# LNA_BFU550.net
KiCad netlist of a schematic drawn in Altium Designer
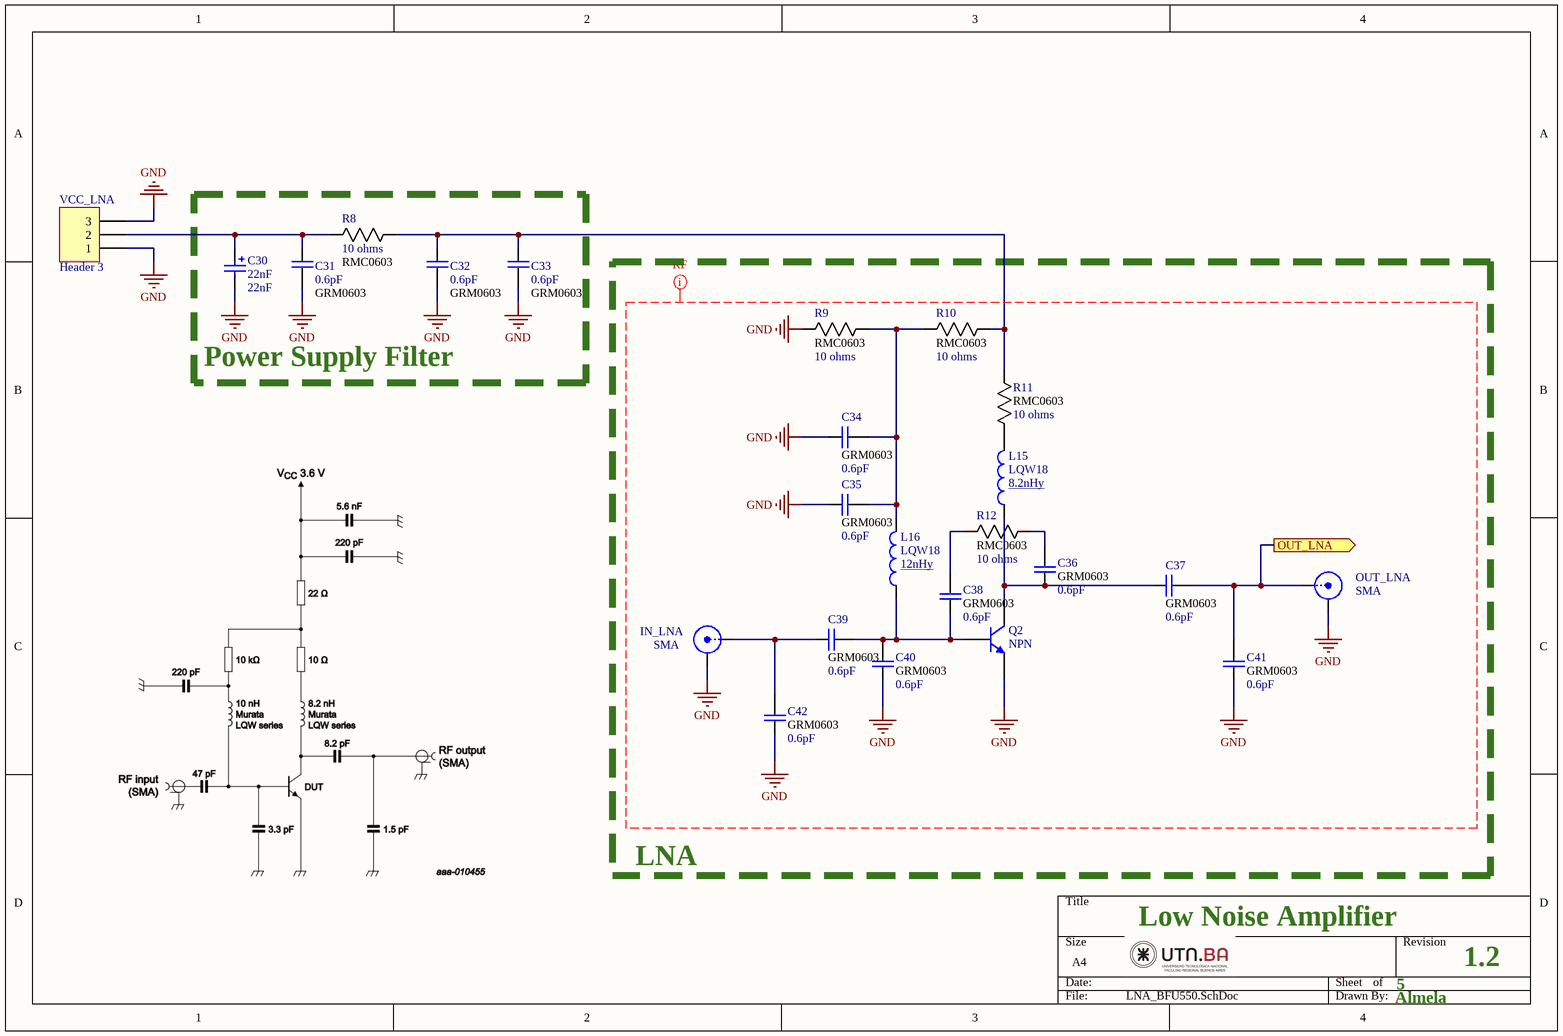
[diagram p0: LNA_BFU550.SchDoc]

(export (version "E")
  (design (tool "Eeschema 10.0.6"))
  (components
    (comp (ref "C30")
      (value "22nF")
      (footprint "6-0805_N")
      (description "Polarized Capacitor (Axial)")
      (fields (field (name "ALTIUM_VALUE") "22nF") (field (name "PUBLISHER") "Altium Limited"))
      (libsource (lib "PCB_Project") (part "Cap Pol2_1"))
    )
    (comp (ref "C31")
      (value "0.6pF")
      (footprint "GRM0603")
      (description "Capacitor GRM18 0603")
      (fields (field (name "Comment") "Cap 0603") (field (name "PUBLISHER") "Altium Limited"))
      (libsource (lib "Radar_RF_EAIII") (part "Cap"))
    )
    (comp (ref "C32")
      (value "0.6pF")
      (footprint "GRM0603")
      (description "Capacitor GRM18 0603")
      (fields (field (name "Comment") "Cap 0603") (field (name "PUBLISHER") "Altium Limited"))
      (libsource (lib "Radar_RF_EAIII") (part "Cap"))
    )
    (comp (ref "C33")
      (value "0.6pF")
      (footprint "GRM0603")
      (description "Capacitor GRM18 0603")
      (fields (field (name "Comment") "Cap 0603") (field (name "PUBLISHER") "Altium Limited"))
      (libsource (lib "Radar_RF_EAIII") (part "Cap"))
    )
    (comp (ref "C34")
      (value "0.6pF")
      (footprint "GRM0603")
      (description "Capacitor GRM18 0603")
      (fields (field (name "Comment") "Cap 0603") (field (name "PUBLISHER") "Altium Limited"))
      (libsource (lib "Radar_RF_EAIII") (part "Cap"))
    )
    (comp (ref "C35")
      (value "0.6pF")
      (footprint "GRM0603")
      (description "Capacitor GRM18 0603")
      (fields (field (name "Comment") "Cap 0603") (field (name "PUBLISHER") "Altium Limited"))
      (libsource (lib "Radar_RF_EAIII") (part "Cap"))
    )
    (comp (ref "C36")
      (value "0.6pF")
      (footprint "GRM0603")
      (description "Capacitor GRM18 0603")
      (fields (field (name "Comment") "Cap 0603") (field (name "PUBLISHER") "Altium Limited"))
      (libsource (lib "Radar_RF_EAIII") (part "Cap"))
    )
    (comp (ref "C37")
      (value "0.6pF")
      (footprint "GRM0603")
      (description "Capacitor GRM18 0603")
      (fields (field (name "Comment") "Cap 0603") (field (name "PUBLISHER") "Altium Limited"))
      (libsource (lib "Radar_RF_EAIII") (part "Cap"))
    )
    (comp (ref "C38")
      (value "0.6pF")
      (footprint "GRM0603")
      (description "Capacitor GRM18 0603")
      (fields (field (name "Comment") "Cap 0603") (field (name "PUBLISHER") "Altium Limited"))
      (libsource (lib "Radar_RF_EAIII") (part "Cap"))
    )
    (comp (ref "C39")
      (value "0.6pF")
      (footprint "GRM0603")
      (description "Capacitor GRM18 0603")
      (fields (field (name "Comment") "Cap 0603") (field (name "PUBLISHER") "Altium Limited"))
      (libsource (lib "Radar_RF_EAIII") (part "Cap"))
    )
    (comp (ref "C40")
      (value "0.6pF")
      (footprint "GRM0603")
      (description "Capacitor GRM18 0603")
      (fields (field (name "Comment") "Cap 0603") (field (name "PUBLISHER") "Altium Limited"))
      (libsource (lib "Radar_RF_EAIII") (part "Cap"))
    )
    (comp (ref "C41")
      (value "0.6pF")
      (footprint "GRM0603")
      (description "Capacitor GRM18 0603")
      (fields (field (name "Comment") "Cap 0603") (field (name "PUBLISHER") "Altium Limited"))
      (libsource (lib "Radar_RF_EAIII") (part "Cap"))
    )
    (comp (ref "C42")
      (value "0.6pF")
      (footprint "GRM0603")
      (description "Capacitor GRM18 0603")
      (fields (field (name "Comment") "Cap 0603") (field (name "PUBLISHER") "Altium Limited"))
      (libsource (lib "Radar_RF_EAIII") (part "Cap"))
    )
    (comp (ref "IN_LNA")
      (value "SMA")
      (footprint "SMA-142-0701-851")
      (description "SMB Straight Connector")
      (fields (field (name "PUBLISHER") "Altium Limited"))
      (libsource (lib "PCB_Project") (part "SMB"))
    )
    (comp (ref "L15")
      (value "LQW18")
      (footprint "INDC1608X100N")
      (description "Inductor LQW Package: 0603 (1608)")
      (fields
        (field (name "MP") "LQW18ANR47J00D")
        (field (name "MF") "Murata")
        (field (name "ALTIUM_VALUE") "8.2nHy")
      )
      (libsource (lib "Radar_RF_EAIII") (part "LQW18_1"))
    )
    (comp (ref "L16")
      (value "LQW18")
      (footprint "INDC1608X100N")
      (description "Inductor LQW Package: 0603 (1608)")
      (fields
        (field (name "MP") "LQW18ANR47J00D")
        (field (name "MF") "Murata")
        (field (name "ALTIUM_VALUE") "12nHy")
      )
      (libsource (lib "Radar_RF_EAIII") (part "LQW18_1"))
    )
    (comp (ref "OUT_LNA")
      (value "SMA")
      (footprint "SMA-142-0701-851")
      (description "SMB Straight Connector")
      (fields (field (name "PUBLISHER") "Altium Limited"))
      (libsource (lib "PCB_Project") (part "SMB"))
    )
    (comp (ref "Q2")
      (value "NPN")
      (footprint "SOT23_N")
      (description "NPN Bipolar Transistor")
      (fields (field (name "PUBLISHER") "Altium Limited"))
      (libsource (lib "Radar_RF_EAIII") (part "BFU550A"))
    )
    (comp (ref "R8")
      (value "10 ohms")
      (footprint "RMC0603")
      (description "Resistor RMC0603")
      (fields (field (name "Comment") "Resistor"))
      (libsource (lib "Radar_RF_EAIII") (part "Resistor"))
    )
    (comp (ref "R9")
      (value "10 ohms")
      (footprint "RMC0603")
      (description "Resistor RMC0603")
      (fields (field (name "Comment") "Resistor"))
      (libsource (lib "Radar_RF_EAIII") (part "Resistor"))
    )
    (comp (ref "R10")
      (value "10 ohms")
      (footprint "RMC0603")
      (description "Resistor RMC0603")
      (fields (field (name "Comment") "Resistor"))
      (libsource (lib "Radar_RF_EAIII") (part "Resistor"))
    )
    (comp (ref "R11")
      (value "10 ohms")
      (footprint "RMC0603")
      (description "Resistor RMC0603")
      (fields (field (name "Comment") "Resistor"))
      (libsource (lib "Radar_RF_EAIII") (part "Resistor"))
    )
    (comp (ref "R12")
      (value "10 ohms")
      (footprint "RMC0603")
      (description "Resistor RMC0603")
      (fields (field (name "Comment") "Resistor"))
      (libsource (lib "Radar_RF_EAIII") (part "Resistor"))
    )
    (comp (ref "VCC_LNA")
      (value "Header 3")
      (footprint "HDR1X3")
      (description "Header, 3-Pin")
      (fields (field (name "PUBLISHER") "Altium Limited"))
      (libsource (lib "Miscellaneous Connectors") (part "Header 3"))
    )
  )
  (nets
    (net (code "1") (name "/OUT_LNA") (class "Default")
      (node (ref "C37") (pin "2") (pinfunction "2_2") (pintype "passive"))
      (node (ref "C41") (pin "2") (pinfunction "2_2") (pintype "passive"))
      (node (ref "OUT_LNA") (pin "1") (pinfunction "X_1") (pintype "passive"))
    )
    (net (code "2") (name "GND") (class "Default")
      (node (ref "C30") (pin "2") (pinfunction "2_2") (pintype "passive"))
      (node (ref "C31") (pin "2") (pinfunction "2_2") (pintype "passive"))
      (node (ref "C32") (pin "2") (pinfunction "2_2") (pintype "passive"))
      (node (ref "C33") (pin "2") (pinfunction "2_2") (pintype "passive"))
      (node (ref "C34") (pin "1") (pinfunction "1_1") (pintype "passive"))
      (node (ref "C35") (pin "1") (pinfunction "1_1") (pintype "passive"))
      (node (ref "C40") (pin "1") (pinfunction "1_1") (pintype "passive"))
      (node (ref "C41") (pin "1") (pinfunction "1_1") (pintype "passive"))
      (node (ref "C42") (pin "1") (pinfunction "1_1") (pintype "passive"))
      (node (ref "IN_LNA") (pin "2") (pinfunction "Y_2") (pintype "passive"))
      (node (ref "OUT_LNA") (pin "2") (pinfunction "Y_2") (pintype "passive"))
      (node (ref "Q2") (pin "2") (pinfunction "E_2") (pintype "passive"))
      (node (ref "R9") (pin "2") (pinfunction "2_2") (pintype "passive"))
      (node (ref "VCC_LNA") (pin "1") (pinfunction "1_1") (pintype "passive"))
      (node (ref "VCC_LNA") (pin "3") (pinfunction "3_3") (pintype "passive"))
    )
    (net (code "3") (name "Net-(C30-Pad1)") (class "Default")
      (node (ref "C30") (pin "1") (pinfunction "1_1") (pintype "passive"))
      (node (ref "C31") (pin "1") (pinfunction "1_1") (pintype "passive"))
      (node (ref "R8") (pin "2") (pinfunction "2_2") (pintype "passive"))
      (node (ref "VCC_LNA") (pin "2") (pinfunction "2_2") (pintype "passive"))
    )
    (net (code "4") (name "Net-(C32-Pad1)") (class "Default")
      (node (ref "C32") (pin "1") (pinfunction "1_1") (pintype "passive"))
      (node (ref "C33") (pin "1") (pinfunction "1_1") (pintype "passive"))
      (node (ref "R10") (pin "2") (pinfunction "2_2") (pintype "passive"))
      (node (ref "R11") (pin "2") (pinfunction "2_2") (pintype "passive"))
      (node (ref "R8") (pin "1") (pinfunction "1_1") (pintype "passive"))
    )
    (net (code "5") (name "Net-(C34-Pad2)") (class "Default")
      (node (ref "C34") (pin "2") (pinfunction "2_2") (pintype "passive"))
      (node (ref "C35") (pin "2") (pinfunction "2_2") (pintype "passive"))
      (node (ref "L16") (pin "2") (pinfunction "2_2") (pintype "passive"))
      (node (ref "R10") (pin "1") (pinfunction "1_1") (pintype "passive"))
      (node (ref "R9") (pin "1") (pinfunction "1_1") (pintype "passive"))
    )
    (net (code "6") (name "Net-(C36-Pad2)") (class "Default")
      (node (ref "C36") (pin "2") (pinfunction "2_2") (pintype "passive"))
      (node (ref "R12") (pin "2") (pinfunction "2_2") (pintype "passive"))
    )
    (net (code "7") (name "Net-(C38-Pad2)") (class "Default")
      (node (ref "C38") (pin "2") (pinfunction "2_2") (pintype "passive"))
      (node (ref "R12") (pin "1") (pinfunction "1_1") (pintype "passive"))
    )
    (net (code "8") (name "Net-(IN_LNA-X)") (class "Default")
      (node (ref "C39") (pin "1") (pinfunction "1_1") (pintype "passive"))
      (node (ref "C42") (pin "2") (pinfunction "2_2") (pintype "passive"))
      (node (ref "IN_LNA") (pin "1") (pinfunction "X_1") (pintype "passive"))
    )
    (net (code "9") (name "Net-(L15-Pad2)") (class "Default")
      (node (ref "L15") (pin "2") (pinfunction "2_2") (pintype "passive"))
      (node (ref "R11") (pin "1") (pinfunction "1_1") (pintype "passive"))
    )
    (net (code "10") (name "Net-(Q2-B)") (class "Default")
      (node (ref "C38") (pin "1") (pinfunction "1_1") (pintype "passive"))
      (node (ref "C39") (pin "2") (pinfunction "2_2") (pintype "passive"))
      (node (ref "C40") (pin "2") (pinfunction "2_2") (pintype "passive"))
      (node (ref "L16") (pin "1") (pinfunction "1_1") (pintype "passive"))
      (node (ref "Q2") (pin "1") (pinfunction "B_1") (pintype "passive"))
    )
    (net (code "11") (name "Net-(Q2-C)") (class "Default")
      (node (ref "C36") (pin "1") (pinfunction "1_1") (pintype "passive"))
      (node (ref "C37") (pin "1") (pinfunction "1_1") (pintype "passive"))
      (node (ref "L15") (pin "1") (pinfunction "1_1") (pintype "passive"))
      (node (ref "Q2") (pin "3") (pinfunction "C_3") (pintype "passive"))
    )
  )
)
